# DummyLoad.net
KiCad netlist of a schematic drawn in EAGLE
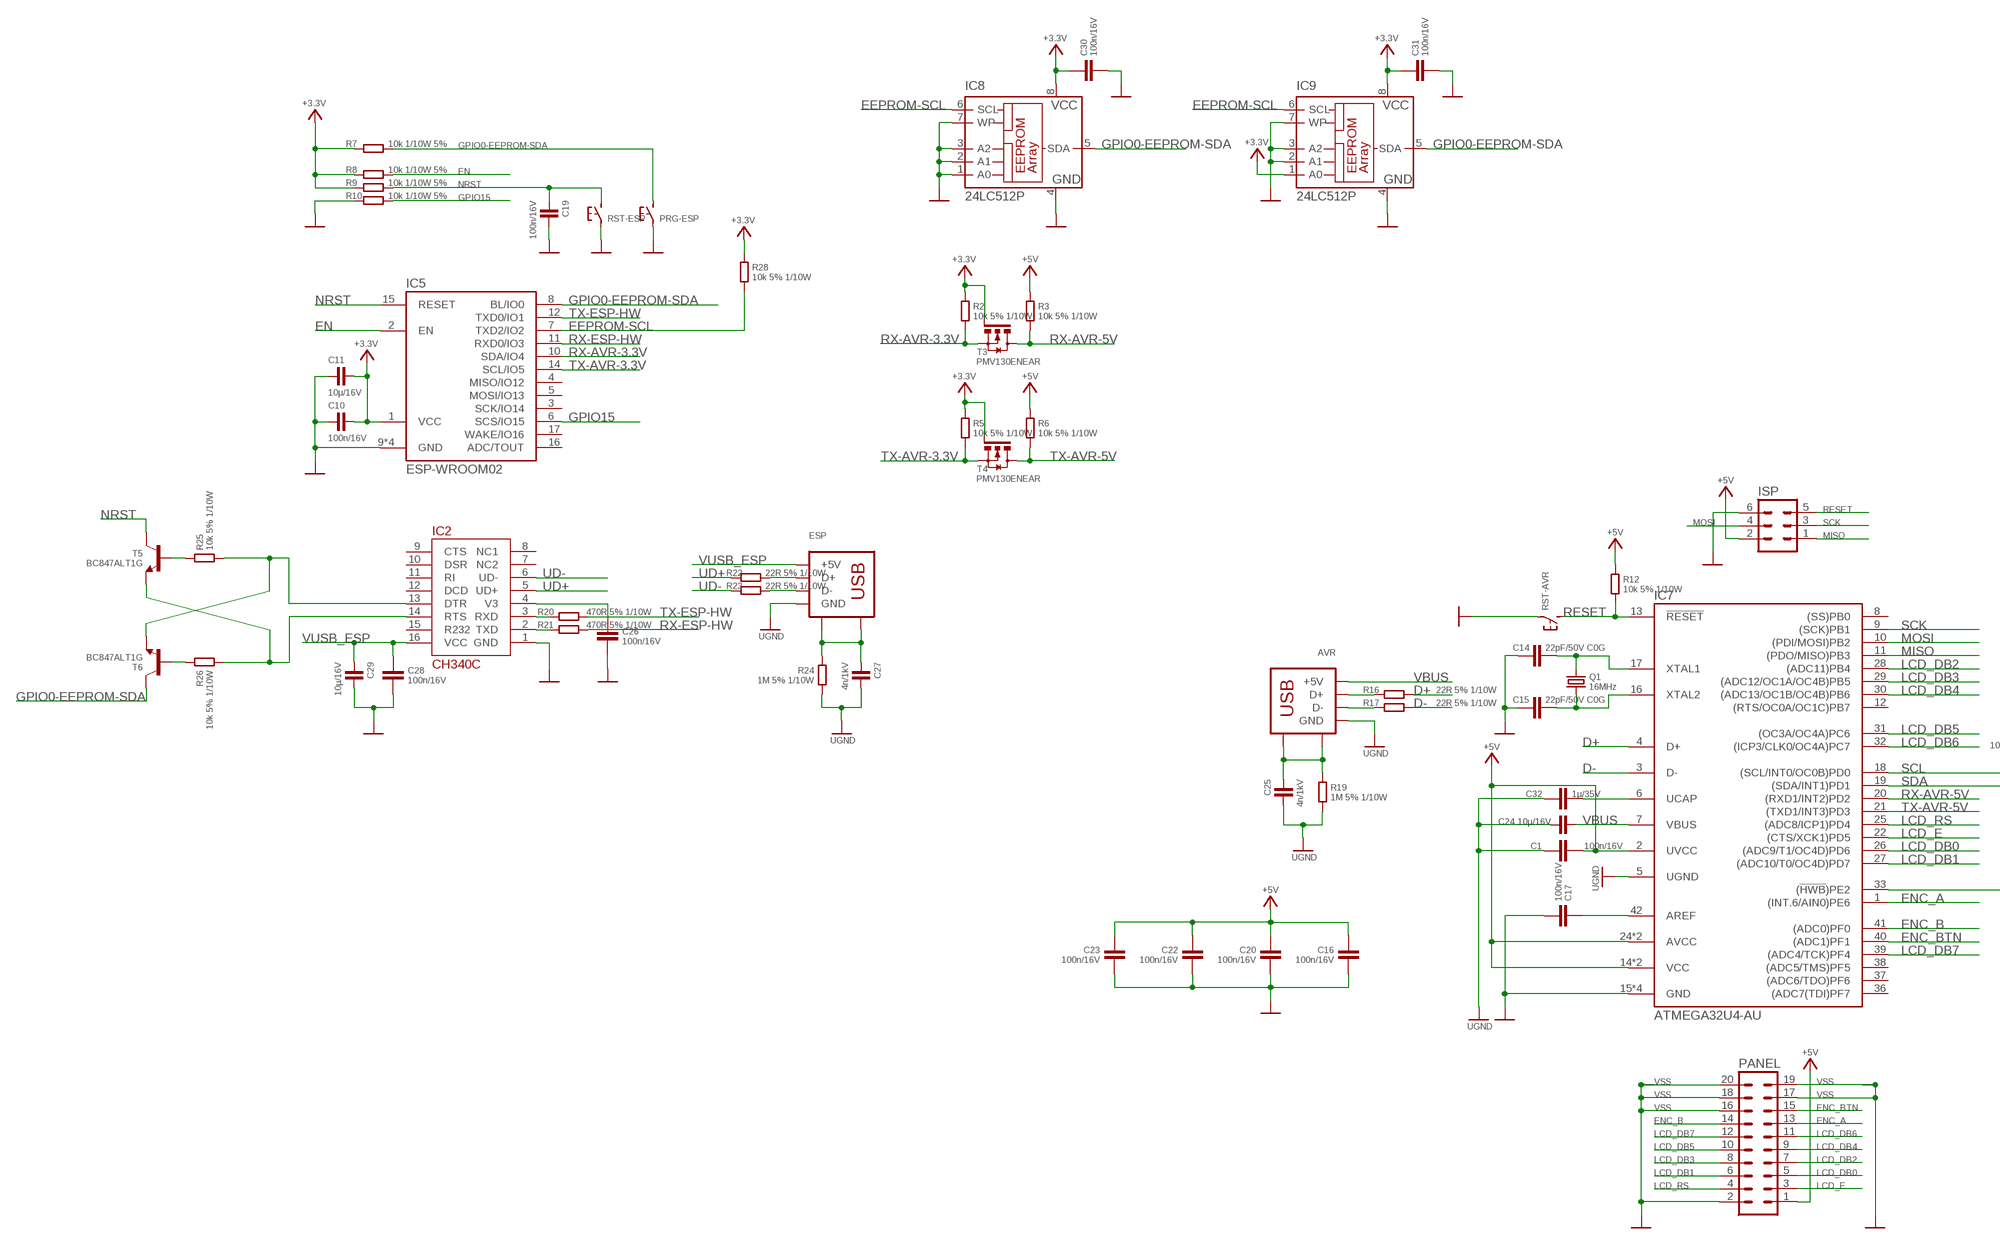
[diagram p0: schematic, sheet 1, part 1 of 2]
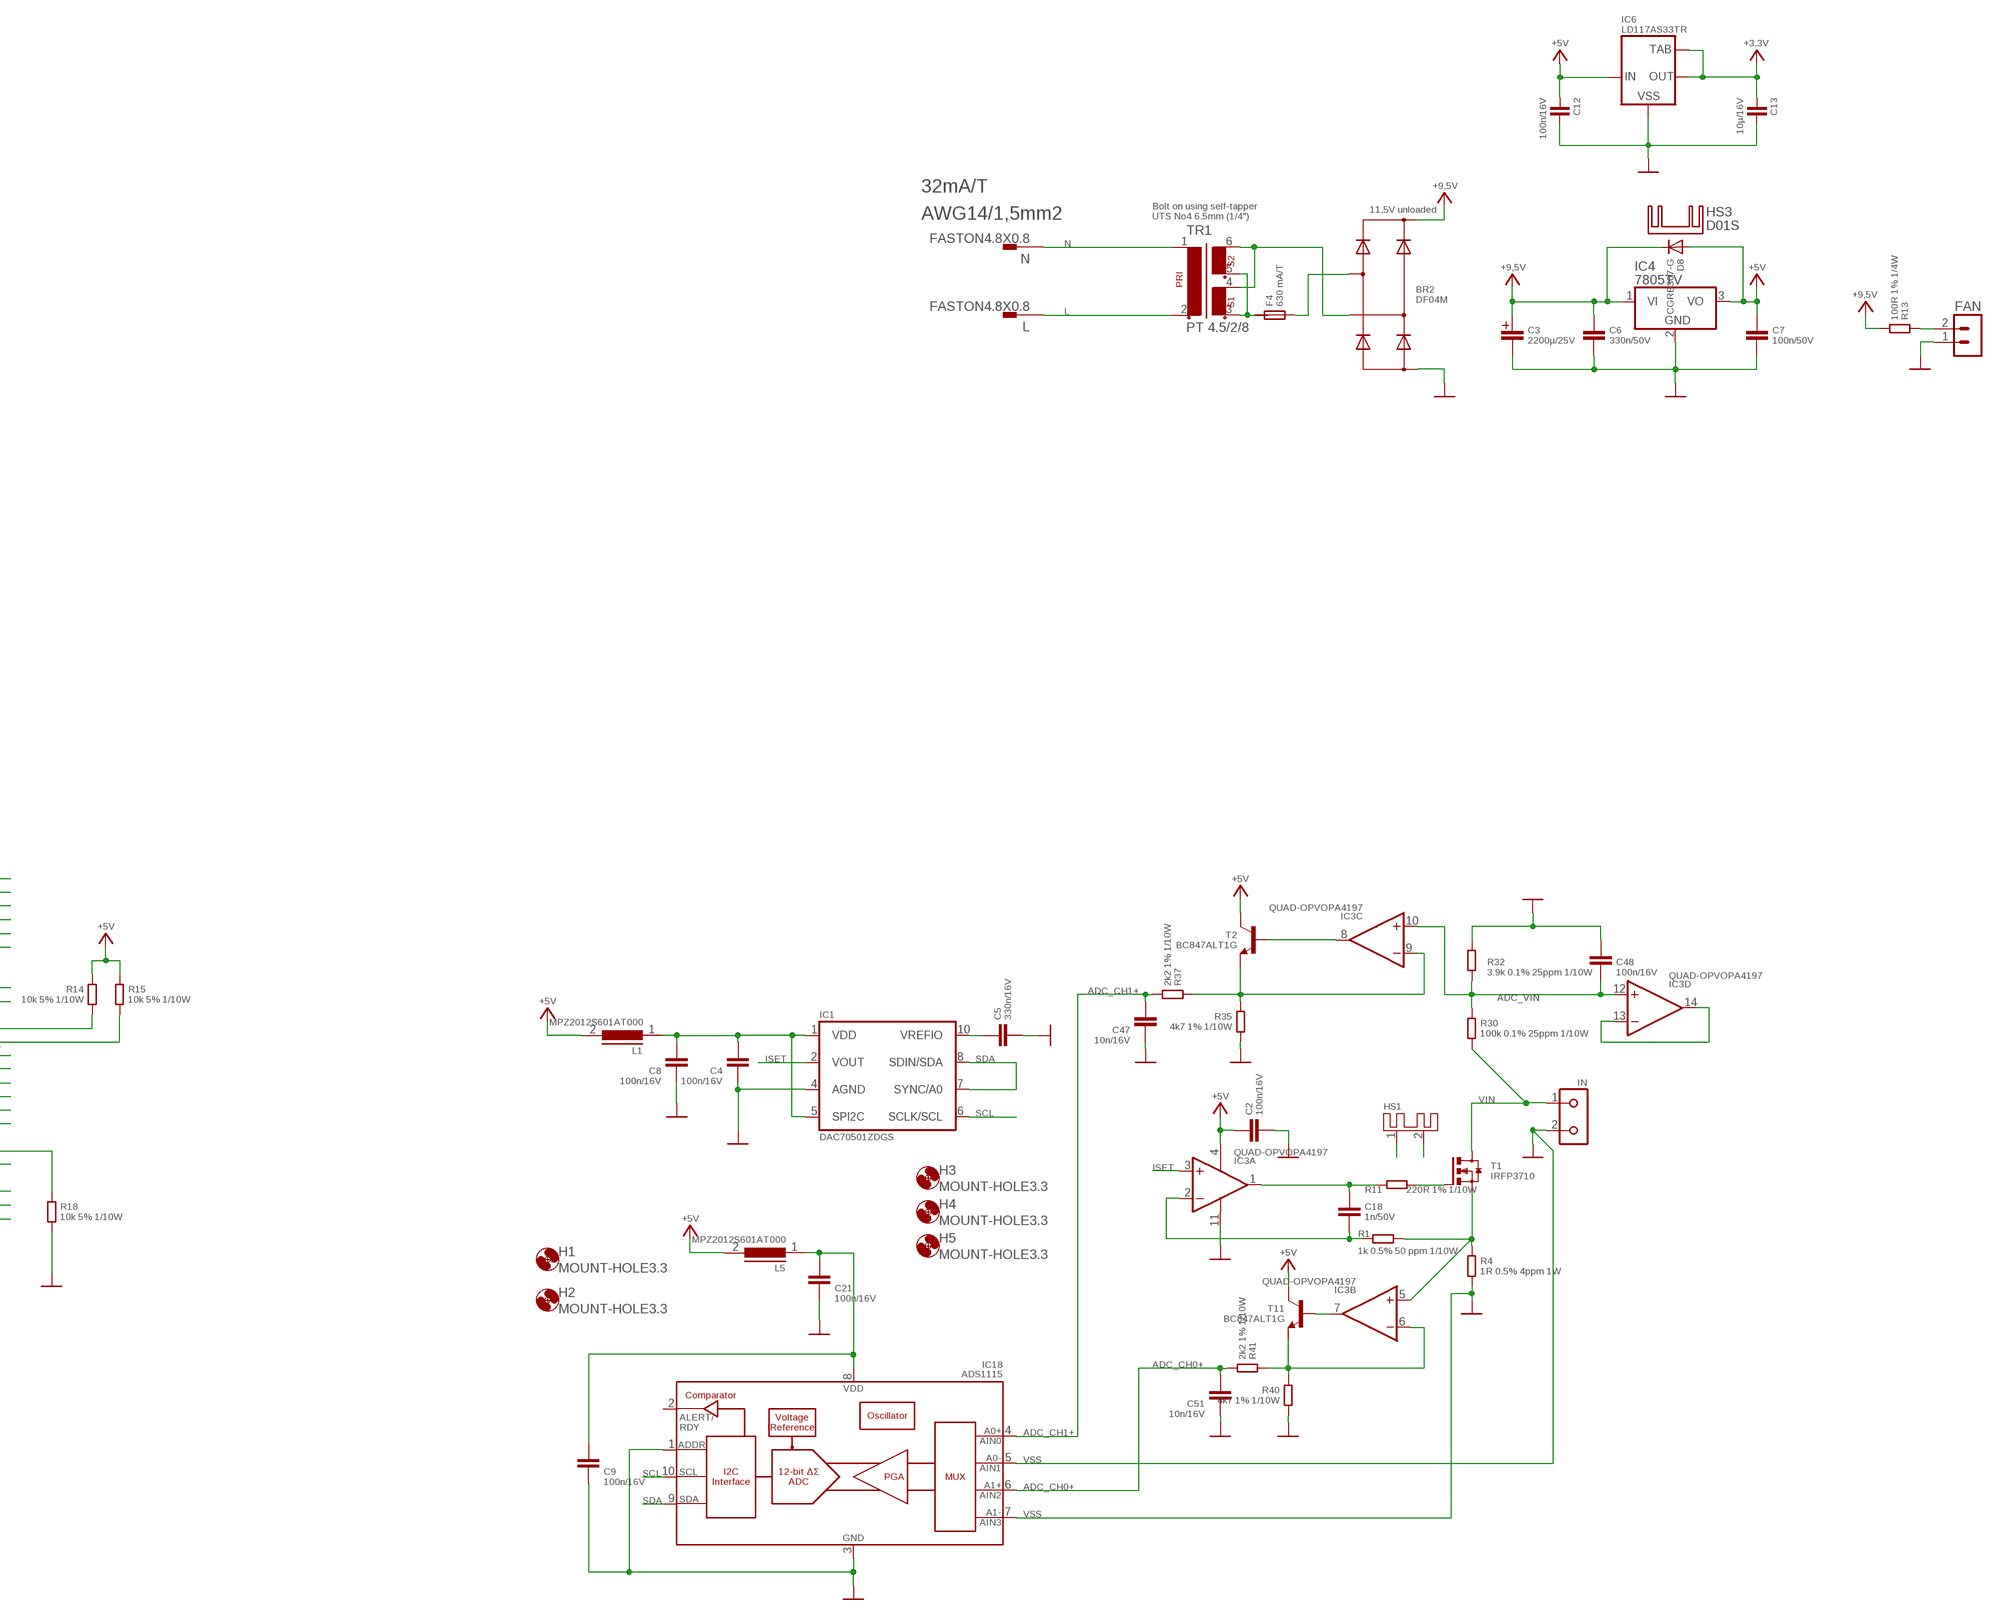
[diagram p1: schematic, sheet 1, part 2 of 2]

(export (version "E")
  (design (tool "Eeschema 10.0.6"))
  (components
    (comp (ref "AVR")
      (value "USBUSB-B")
      (footprint "eagle-import:USB-B")
      (libsource (lib "eagle-import") (part "USBUSB-B"))
    )
    (comp (ref "BR2")
      (value "DF04M")
      (footprint "eagle-import:BR-DIL2")
      (libsource (lib "eagle-import") (part "BRDIL2"))
    )
    (comp (ref "C1")
      (value "100n/16V")
      (footprint "eagle-import:0805")
      (libsource (lib "eagle-import") (part "CC/0805"))
    )
    (comp (ref "C2")
      (value "100n/16V")
      (footprint "eagle-import:0805")
      (libsource (lib "eagle-import") (part "CC/0805"))
    )
    (comp (ref "C3")
      (value "2200µ/25V")
      (footprint "eagle-import:C+_5_12.5")
      (libsource (lib "eagle-import") (part "C+5/12.5"))
    )
    (comp (ref "C4")
      (value "100n/16V")
      (footprint "eagle-import:0805")
      (libsource (lib "eagle-import") (part "CC/0805"))
    )
    (comp (ref "C5")
      (value "330n/16V")
      (footprint "eagle-import:0805")
      (libsource (lib "eagle-import") (part "CC/0805"))
    )
    (comp (ref "C6")
      (value "330n/50V")
      (footprint "eagle-import:0805")
      (libsource (lib "eagle-import") (part "CC/0805"))
    )
    (comp (ref "C7")
      (value "100n/50V")
      (footprint "eagle-import:0805")
      (libsource (lib "eagle-import") (part "CC/0805"))
    )
    (comp (ref "C8")
      (value "100n/16V")
      (footprint "eagle-import:0805")
      (libsource (lib "eagle-import") (part "CC/0805"))
    )
    (comp (ref "C9")
      (value "100n/16V")
      (footprint "eagle-import:0805")
      (libsource (lib "eagle-import") (part "CC/0805"))
    )
    (comp (ref "C10")
      (value "100n/16V")
      (footprint "eagle-import:C0805")
      (libsource (lib "eagle-import") (part "CAPACITOR-0805"))
    )
    (comp (ref "C11")
      (value "10µ/16V")
      (footprint "eagle-import:C1210")
      (libsource (lib "eagle-import") (part "CAPACITOR-1210"))
    )
    (comp (ref "C12")
      (value "100n/16V")
      (footprint "eagle-import:C0805")
      (libsource (lib "eagle-import") (part "CAPACITOR-0805"))
    )
    (comp (ref "C13")
      (value "10µ/16V")
      (footprint "eagle-import:C1210")
      (libsource (lib "eagle-import") (part "CAPACITOR-1210"))
    )
    (comp (ref "C14")
      (value "22pF/50V C0G")
      (footprint "eagle-import:0805")
      (libsource (lib "eagle-import") (part "CC/0805"))
    )
    (comp (ref "C15")
      (value "22pF/50V C0G")
      (footprint "eagle-import:0805")
      (libsource (lib "eagle-import") (part "CC/0805"))
    )
    (comp (ref "C16")
      (value "100n/16V")
      (footprint "eagle-import:0805")
      (libsource (lib "eagle-import") (part "CC/0805"))
    )
    (comp (ref "C17")
      (value "100n/16V")
      (footprint "eagle-import:0805")
      (libsource (lib "eagle-import") (part "CC/0805"))
    )
    (comp (ref "C18")
      (value "1n/50V")
      (footprint "eagle-import:0805")
      (libsource (lib "eagle-import") (part "CC/0805"))
    )
    (comp (ref "C19")
      (value "100n/16V")
      (footprint "eagle-import:C0805")
      (libsource (lib "eagle-import") (part "CAPACITOR-0805"))
    )
    (comp (ref "C20")
      (value "100n/16V")
      (footprint "eagle-import:0805")
      (libsource (lib "eagle-import") (part "CC/0805"))
    )
    (comp (ref "C21")
      (value "100n/16V")
      (footprint "eagle-import:0805")
      (libsource (lib "eagle-import") (part "CC/0805"))
    )
    (comp (ref "C22")
      (value "100n/16V")
      (footprint "eagle-import:0805")
      (libsource (lib "eagle-import") (part "CC/0805"))
    )
    (comp (ref "C23")
      (value "100n/16V")
      (footprint "eagle-import:0805")
      (libsource (lib "eagle-import") (part "CC/0805"))
    )
    (comp (ref "C24")
      (value "10µ/16V")
      (footprint "eagle-import:C1210")
      (libsource (lib "eagle-import") (part "CAPACITOR-1210"))
    )
    (comp (ref "C25")
      (value "4n/1kV")
      (footprint "eagle-import:C1206")
      (libsource (lib "eagle-import") (part "CAPACITOR-1206"))
    )
    (comp (ref "C26")
      (value "100n/16V")
      (footprint "eagle-import:0805")
      (libsource (lib "eagle-import") (part "CC/0805"))
    )
    (comp (ref "C27")
      (value "4n/1kV")
      (footprint "eagle-import:C1206")
      (libsource (lib "eagle-import") (part "CAPACITOR-1206"))
    )
    (comp (ref "C28")
      (value "100n/16V")
      (footprint "eagle-import:0805")
      (libsource (lib "eagle-import") (part "CC/0805"))
    )
    (comp (ref "C29")
      (value "10µ/16V")
      (footprint "eagle-import:C1210")
      (libsource (lib "eagle-import") (part "CAPACITOR-1210"))
    )
    (comp (ref "C30")
      (value "100n/16V")
      (footprint "eagle-import:0805")
      (libsource (lib "eagle-import") (part "CC/0805"))
    )
    (comp (ref "C31")
      (value "100n/16V")
      (footprint "eagle-import:0805")
      (libsource (lib "eagle-import") (part "CC/0805"))
    )
    (comp (ref "C32")
      (value "1µ/35V")
      (footprint "eagle-import:0805")
      (libsource (lib "eagle-import") (part "CC/0805"))
    )
    (comp (ref "C47")
      (value "10n/16V")
      (footprint "eagle-import:0805")
      (libsource (lib "eagle-import") (part "CC/0805"))
    )
    (comp (ref "C48")
      (value "100n/16V")
      (footprint "eagle-import:0805")
      (libsource (lib "eagle-import") (part "CC/0805"))
    )
    (comp (ref "C51")
      (value "10n/16V")
      (footprint "eagle-import:0805")
      (libsource (lib "eagle-import") (part "CC/0805"))
    )
    (comp (ref "D8")
      (value "CGRB307-G")
      (footprint "eagle-import:DO214AA-CGRB307-G")
      (libsource (lib "eagle-import") (part "DWIDE"))
    )
    (comp (ref "ESP")
      (value "USBUSB-B")
      (footprint "eagle-import:USB-B")
      (libsource (lib "eagle-import") (part "USBUSB-B"))
    )
    (comp (ref "F4")
      (value "630 mA/T")
      (footprint "eagle-import:F5X20")
      (libsource (lib "eagle-import") (part "F5X20"))
    )
    (comp (ref "FAN")
      (value "JST-PH-2.0-2P")
      (footprint "eagle-import:JST-PH-2.0-2P")
      (libsource (lib "eagle-import") (part "JST-PH-2.0-2P"))
    )
    (comp (ref "H1")
      (value "MOUNT-HOLE3.3")
      (footprint "eagle-import:3,3")
      (libsource (lib "eagle-import") (part "MOUNT-HOLE3.3"))
    )
    (comp (ref "H2")
      (value "MOUNT-HOLE3.3")
      (footprint "eagle-import:3,3")
      (libsource (lib "eagle-import") (part "MOUNT-HOLE3.3"))
    )
    (comp (ref "H3")
      (value "MOUNT-HOLE3.3")
      (footprint "eagle-import:3,3")
      (libsource (lib "eagle-import") (part "MOUNT-HOLE3.3"))
    )
    (comp (ref "H4")
      (value "MOUNT-HOLE3.3")
      (footprint "eagle-import:3,3")
      (libsource (lib "eagle-import") (part "MOUNT-HOLE3.3"))
    )
    (comp (ref "H5")
      (value "MOUNT-HOLE3.3")
      (footprint "eagle-import:3,3")
      (libsource (lib "eagle-import") (part "MOUNT-HOLE3.3"))
    )
    (comp (ref "HS1")
      (value "HSCR201-50")
      (footprint "eagle-import:CR201-50")
      (libsource (lib "eagle-import") (part "HSCR201-50"))
    )
    (comp (ref "HS3")
      (value "D01S")
      (footprint "eagle-import:D01S")
      (libsource (lib "eagle-import") (part "D01S"))
    )
    (comp (ref "IC1")
      (value "DAC70501ZDGS")
      (footprint "eagle-import:VSSOP10")
      (libsource (lib "eagle-import") (part "DAC70501"))
    )
    (comp (ref "IC2")
      (value "CH340C")
      (footprint "eagle-import:SOP16")
      (libsource (lib "eagle-import") (part "CH340C"))
    )
    (comp (ref "IC3")
      (value "QUAD-OPVOPA4197")
      (footprint "eagle-import:SO14")
      (fields (field (name "OC_MOUSER") "595-OPA4197IDR"))
      (libsource (lib "eagle-import") (part "QUAD-OPVOPA4197"))
    )
    (comp (ref "IC4")
      (value "7805TV")
      (footprint "eagle-import:TO220V")
      (libsource (lib "eagle-import") (part "78TV05"))
    )
    (comp (ref "IC5")
      (value "ESP-WROOM02")
      (footprint "eagle-import:ESP-WROOM02")
      (libsource (lib "eagle-import") (part "ESP-WROOM02"))
    )
    (comp (ref "IC6")
      (value "LD117AS33TR")
      (footprint "eagle-import:SOT223")
      (libsource (lib "eagle-import") (part "LD117A?S33TR"))
    )
    (comp (ref "IC7")
      (value "ATMEGA32U4-AU")
      (footprint "eagle-import:TQFP44")
      (libsource (lib "eagle-import") (part "ATMEGA32U4-AU"))
    )
    (comp (ref "IC8")
      (value "24LC512P")
      (footprint "eagle-import:DIL8")
      (fields (field (name "MF") "MICROCHIP") (field (name "MPN") "24LC256-E/P"))
      (libsource (lib "eagle-import") (part "24PLC256"))
    )
    (comp (ref "IC9")
      (value "24LC512P")
      (footprint "eagle-import:DIL8")
      (fields (field (name "MF") "MICROCHIP") (field (name "MPN") "24LC256-E/P"))
      (libsource (lib "eagle-import") (part "24PLC256"))
    )
    (comp (ref "IC18")
      (value "ADS1115")
      (footprint "eagle-import:VSSOP10")
      (libsource (lib "eagle-import") (part "ADS1015VSSOP10"))
    )
    (comp (ref "IN")
      (value "KL2691311500002")
      (footprint "eagle-import:KL2-691311500002")
      (libsource (lib "eagle-import") (part "KL2691311500002"))
    )
    (comp (ref "ISP")
      (value "ML6")
      (footprint "eagle-import:ML6")
      (libsource (lib "eagle-import") (part "ML6"))
    )
    (comp (ref "L")
      (value "FASTON4.8X0.8")
      (footprint "eagle-import:FASTON-4.8X0.8")
      (libsource (lib "eagle-import") (part "FASTON4.8X0.8"))
    )
    (comp (ref "L1")
      (value "MPZ2012S601AT000")
      (footprint "eagle-import:C0805K@1")
      (libsource (lib "eagle-import") (part "L0805"))
    )
    (comp (ref "L5")
      (value "MPZ2012S601AT000")
      (footprint "eagle-import:C0805K@1")
      (libsource (lib "eagle-import") (part "L0805"))
    )
    (comp (ref "N")
      (value "FASTON4.8X0.8")
      (footprint "eagle-import:FASTON-4.8X0.8")
      (libsource (lib "eagle-import") (part "FASTON4.8X0.8"))
    )
    (comp (ref "PANEL")
      (value "MA10-2")
      (footprint "eagle-import:MA10-2")
      (libsource (lib "eagle-import") (part "MA10-2"))
    )
    (comp (ref "PRG-ESP")
      (value "TS1B3F-10XX")
      (footprint "eagle-import:B3F-10XX")
      (libsource (lib "eagle-import") (part "TS1B3F-10XX"))
    )
    (comp (ref "Q1")
      (value "16MHz")
      (footprint "eagle-import:Q-5X3.2MM-TXC-7A.SERIES")
      (libsource (lib "eagle-import") (part "Q5X3.2MM-TXC-7A-SERIES"))
    )
    (comp (ref "R1")
      (value "1k 0.5% 50 ppm 1/10W")
      (footprint "eagle-import:C0805K")
      (libsource (lib "eagle-import") (part "R-SMD0805"))
    )
    (comp (ref "R2")
      (value "10k 5% 1/10W")
      (footprint "eagle-import:C0805K")
      (libsource (lib "eagle-import") (part "R-SMD0805"))
    )
    (comp (ref "R3")
      (value "10k 5% 1/10W")
      (footprint "eagle-import:C0805K")
      (libsource (lib "eagle-import") (part "R-SMD0805"))
    )
    (comp (ref "R4")
      (value "1R 0.5% 4ppm 1W")
      (footprint "eagle-import:R-SHUNT-VSR")
      (libsource (lib "eagle-import") (part "R-SHUNTVSR"))
    )
    (comp (ref "R5")
      (value "10k 5% 1/10W")
      (footprint "eagle-import:C0805K")
      (libsource (lib "eagle-import") (part "R-SMD0805"))
    )
    (comp (ref "R6")
      (value "10k 5% 1/10W")
      (footprint "eagle-import:C0805K")
      (libsource (lib "eagle-import") (part "R-SMD0805"))
    )
    (comp (ref "R7")
      (value "10k 1/10W 5%")
      (footprint "eagle-import:C0805K")
      (libsource (lib "eagle-import") (part "R-SMD0805"))
    )
    (comp (ref "R8")
      (value "10k 1/10W 5%")
      (footprint "eagle-import:C0805K")
      (libsource (lib "eagle-import") (part "R-SMD0805"))
    )
    (comp (ref "R9")
      (value "10k 1/10W 5%")
      (footprint "eagle-import:C0805K")
      (libsource (lib "eagle-import") (part "R-SMD0805"))
    )
    (comp (ref "R10")
      (value "10k 1/10W 5%")
      (footprint "eagle-import:C0805K")
      (libsource (lib "eagle-import") (part "R-SMD0805"))
    )
    (comp (ref "R11")
      (value "220R 1% 1/10W")
      (footprint "eagle-import:C0805K")
      (libsource (lib "eagle-import") (part "R-SMD0805"))
    )
    (comp (ref "R12")
      (value "10k 5% 1/10W")
      (footprint "eagle-import:C0805K")
      (libsource (lib "eagle-import") (part "R-SMD0805"))
    )
    (comp (ref "R13")
      (value "100R 1% 1/4W")
      (footprint "eagle-import:C0805K")
      (libsource (lib "eagle-import") (part "R-SMD0805"))
    )
    (comp (ref "R14")
      (value "10k 5% 1/10W")
      (footprint "eagle-import:C0805K")
      (libsource (lib "eagle-import") (part "R-SMD0805"))
    )
    (comp (ref "R15")
      (value "10k 5% 1/10W")
      (footprint "eagle-import:C0805K")
      (libsource (lib "eagle-import") (part "R-SMD0805"))
    )
    (comp (ref "R16")
      (value "22R 5% 1/10W")
      (footprint "eagle-import:C0805K")
      (libsource (lib "eagle-import") (part "R-SMD0805"))
    )
    (comp (ref "R17")
      (value "22R 5% 1/10W")
      (footprint "eagle-import:C0805K")
      (libsource (lib "eagle-import") (part "R-SMD0805"))
    )
    (comp (ref "R18")
      (value "10k 5% 1/10W")
      (footprint "eagle-import:C0805K")
      (libsource (lib "eagle-import") (part "R-SMD0805"))
    )
    (comp (ref "R19")
      (value "1M 5% 1/10W")
      (footprint "eagle-import:C0805K")
      (libsource (lib "eagle-import") (part "R-SMD0805"))
    )
    (comp (ref "R20")
      (value "470R 5% 1/10W")
      (footprint "eagle-import:C0805K")
      (libsource (lib "eagle-import") (part "R-SMD0805"))
    )
    (comp (ref "R21")
      (value "470R 5% 1/10W")
      (footprint "eagle-import:C0805K")
      (libsource (lib "eagle-import") (part "R-SMD0805"))
    )
    (comp (ref "R22")
      (value "22R 5% 1/10W")
      (footprint "eagle-import:C0805K")
      (libsource (lib "eagle-import") (part "R-SMD0805"))
    )
    (comp (ref "R23")
      (value "22R 5% 1/10W")
      (footprint "eagle-import:C0805K")
      (libsource (lib "eagle-import") (part "R-SMD0805"))
    )
    (comp (ref "R24")
      (value "1M 5% 1/10W")
      (footprint "eagle-import:C0805K")
      (libsource (lib "eagle-import") (part "R-SMD0805"))
    )
    (comp (ref "R25")
      (value "10k 5% 1/10W")
      (footprint "eagle-import:C0805K")
      (libsource (lib "eagle-import") (part "R-SMD0805"))
    )
    (comp (ref "R26")
      (value "10k 5% 1/10W")
      (footprint "eagle-import:C0805K")
      (libsource (lib "eagle-import") (part "R-SMD0805"))
    )
    (comp (ref "R28")
      (value "10k 5% 1/10W")
      (footprint "eagle-import:C0805K")
      (libsource (lib "eagle-import") (part "R-SMD0805"))
    )
    (comp (ref "R30")
      (value "100k 0.1% 25ppm 1/10W")
      (footprint "eagle-import:C0805K")
      (libsource (lib "eagle-import") (part "R-SMD0805"))
    )
    (comp (ref "R32")
      (value "3.9k 0.1% 25ppm 1/10W")
      (footprint "eagle-import:C0805K")
      (libsource (lib "eagle-import") (part "R-SMD0805"))
    )
    (comp (ref "R35")
      (value "4k7 1% 1/10W")
      (footprint "eagle-import:C0805K")
      (libsource (lib "eagle-import") (part "R-SMD0805"))
    )
    (comp (ref "R37")
      (value "2k2 1% 1/10W")
      (footprint "eagle-import:C0805K")
      (libsource (lib "eagle-import") (part "R-SMD0805"))
    )
    (comp (ref "R40")
      (value "4k7 1% 1/10W")
      (footprint "eagle-import:C0805K")
      (libsource (lib "eagle-import") (part "R-SMD0805"))
    )
    (comp (ref "R41")
      (value "2k2 1% 1/10W")
      (footprint "eagle-import:C0805K")
      (libsource (lib "eagle-import") (part "R-SMD0805"))
    )
    (comp (ref "RST-AVR")
      (value "TS1B3F-10XX")
      (footprint "eagle-import:B3F-10XX")
      (libsource (lib "eagle-import") (part "TS1B3F-10XX"))
    )
    (comp (ref "RST-ESP")
      (value "TS1B3F-10XX")
      (footprint "eagle-import:B3F-10XX")
      (libsource (lib "eagle-import") (part "TS1B3F-10XX"))
    )
    (comp (ref "T1")
      (value "IRFP3710")
      (footprint "eagle-import:TOP3AV")
      (libsource (lib "eagle-import") (part "T-NMOSTO247"))
    )
    (comp (ref "T2")
      (value "BC847ALT1G")
      (footprint "eagle-import:SOT23-BEC")
      (libsource (lib "eagle-import") (part "T-NPNSOT23-BEC"))
    )
    (comp (ref "T3")
      (value "PMV130ENEAR")
      (footprint "eagle-import:SOT23")
      (libsource (lib "eagle-import") (part "T-NMOSIRLML2502PBF"))
    )
    (comp (ref "T4")
      (value "PMV130ENEAR")
      (footprint "eagle-import:SOT23")
      (libsource (lib "eagle-import") (part "T-NMOSIRLML2502PBF"))
    )
    (comp (ref "T5")
      (value "BC847ALT1G")
      (footprint "eagle-import:SOT23-BEC")
      (libsource (lib "eagle-import") (part "T-NPNSOT23-BEC"))
    )
    (comp (ref "T6")
      (value "BC847ALT1G")
      (footprint "eagle-import:SOT23-BEC")
      (libsource (lib "eagle-import") (part "T-NPNSOT23-BEC"))
    )
    (comp (ref "T11")
      (value "BC847ALT1G")
      (footprint "eagle-import:SOT23-BEC")
      (libsource (lib "eagle-import") (part "T-NPNSOT23-BEC"))
    )
    (comp (ref "TR1")
      (value "PT 4.5/2/8")
      (footprint "eagle-import:PT_4,5_2_..")
      (libsource (lib "eagle-import") (part "PT4,5/2/.."))
    )
  )
  (nets
    (net (code "1") (name "+3.3V") (class "Default")
      (node (ref "C10") (pin "2") (pinfunction "2_2") (pintype "passive"))
      (node (ref "C11") (pin "2") (pinfunction "2_2") (pintype "passive"))
      (node (ref "C13") (pin "1") (pinfunction "1_1") (pintype "passive"))
      (node (ref "C30") (pin "1") (pinfunction "1_1") (pintype "passive"))
      (node (ref "C31") (pin "1") (pinfunction "1_1") (pintype "passive"))
      (node (ref "IC5") (pin "1") (pinfunction "VCC_1") (pintype "power_in"))
      (node (ref "IC6") (pin "2") (pinfunction "OUT_2") (pintype "passive"))
      (node (ref "IC6") (pin "4") (pinfunction "OUT1_4") (pintype "passive"))
      (node (ref "IC8") (pin "8") (pinfunction "VCC_8") (pintype "power_in"))
      (node (ref "IC9") (pin "1") (pinfunction "A0_1") (pintype "input"))
      (node (ref "IC9") (pin "8") (pinfunction "VCC_8") (pintype "power_in"))
      (node (ref "R2") (pin "1") (pinfunction "1_1") (pintype "passive"))
      (node (ref "R28") (pin "1") (pinfunction "1_1") (pintype "passive"))
      (node (ref "R5") (pin "1") (pinfunction "1_1") (pintype "passive"))
      (node (ref "R7") (pin "1") (pinfunction "1_1") (pintype "passive"))
      (node (ref "R8") (pin "1") (pinfunction "1_1") (pintype "passive"))
      (node (ref "R9") (pin "1") (pinfunction "1_1") (pintype "passive"))
      (node (ref "T3") (pin "1") (pinfunction "G_1") (pintype "passive"))
      (node (ref "T4") (pin "1") (pinfunction "G_1") (pintype "passive"))
    )
    (net (code "2") (name "+5V") (class "Default")
      (node (ref "C1") (pin "2") (pinfunction "2_2") (pintype "passive"))
      (node (ref "C12") (pin "1") (pinfunction "1_1") (pintype "passive"))
      (node (ref "C16") (pin "1") (pinfunction "1_1") (pintype "passive"))
      (node (ref "C2") (pin "1") (pinfunction "1_1") (pintype "passive"))
      (node (ref "C20") (pin "1") (pinfunction "1_1") (pintype "passive"))
      (node (ref "C22") (pin "1") (pinfunction "1_1") (pintype "passive"))
      (node (ref "C23") (pin "1") (pinfunction "1_1") (pintype "passive"))
      (node (ref "C7") (pin "1") (pinfunction "1_1") (pintype "passive"))
      (node (ref "D8") (pin "A") (pinfunction "A_A") (pintype "passive"))
      (node (ref "IC3") (pin "4") (pinfunction "V+_4") (pintype "power_in"))
      (node (ref "IC4") (pin "3") (pinfunction "VO_3") (pintype "passive"))
      (node (ref "IC6") (pin "3") (pinfunction "IN_3") (pintype "input"))
      (node (ref "IC7") (pin "14") (pinfunction "VCC_14") (pintype "power_in"))
      (node (ref "IC7") (pin "2") (pinfunction "UVCC_2") (pintype "power_in"))
      (node (ref "IC7") (pin "24") (pinfunction "AVCC_24") (pintype "power_in"))
      (node (ref "IC7") (pin "34") (pinfunction "VCC_34") (pintype "power_in"))
      (node (ref "IC7") (pin "44") (pinfunction "AVCC_44") (pintype "power_in"))
      (node (ref "ISP") (pin "2") (pinfunction "2_2") (pintype "passive"))
      (node (ref "L1") (pin "2") (pinfunction "2_2") (pintype "passive"))
      (node (ref "L5") (pin "2") (pinfunction "2_2") (pintype "passive"))
      (node (ref "PANEL") (pin "1") (pinfunction "1_1") (pintype "passive"))
      (node (ref "R12") (pin "1") (pinfunction "1_1") (pintype "passive"))
      (node (ref "R14") (pin "1") (pinfunction "1_1") (pintype "passive"))
      (node (ref "R15") (pin "1") (pinfunction "1_1") (pintype "passive"))
      (node (ref "R3") (pin "1") (pinfunction "1_1") (pintype "passive"))
      (node (ref "R6") (pin "1") (pinfunction "1_1") (pintype "passive"))
      (node (ref "T11") (pin "C") (pinfunction "C_C") (pintype "passive"))
      (node (ref "T2") (pin "C") (pinfunction "C_C") (pintype "passive"))
    )
    (net (code "3") (name "+9,5V") (class "Default")
      (node (ref "BR2") (pin "DC+") (pinfunction "DC+_DC+") (pintype "passive"))
      (node (ref "C3") (pin "+") (pinfunction "+_+") (pintype "passive"))
      (node (ref "C6") (pin "1") (pinfunction "1_1") (pintype "passive"))
      (node (ref "D8") (pin "C") (pinfunction "C_C") (pintype "passive"))
      (node (ref "IC4") (pin "1") (pinfunction "VI_1") (pintype "input"))
      (node (ref "R13") (pin "2") (pinfunction "2_2") (pintype "passive"))
    )
    (net (code "4") (name "/ADC_CH0+") (class "Default")
      (node (ref "C51") (pin "1") (pinfunction "1_1") (pintype "passive"))
      (node (ref "IC18") (pin "6") (pinfunction "AIN2_6") (pintype "bidirectional"))
      (node (ref "R41") (pin "2") (pinfunction "2_2") (pintype "passive"))
    )
    (net (code "5") (name "/ADC_CH1+") (class "Default")
      (node (ref "C47") (pin "1") (pinfunction "1_1") (pintype "passive"))
      (node (ref "IC18") (pin "4") (pinfunction "AIN0_4") (pintype "bidirectional"))
      (node (ref "R37") (pin "2") (pinfunction "2_2") (pintype "passive"))
    )
    (net (code "6") (name "/ADC_VIN") (class "Default")
      (node (ref "C48") (pin "2") (pinfunction "2_2") (pintype "passive"))
      (node (ref "IC3") (pin "10") (pinfunction "+IN_10") (pintype "input"))
      (node (ref "IC3") (pin "12") (pinfunction "+IN_12") (pintype "input"))
      (node (ref "R30") (pin "1") (pinfunction "1_1") (pintype "passive"))
      (node (ref "R32") (pin "2") (pinfunction "2_2") (pintype "passive"))
    )
    (net (code "7") (name "/D+") (class "Default")
      (node (ref "IC7") (pin "4") (pinfunction "D+_4") (pintype "bidirectional"))
      (node (ref "R16") (pin "1") (pinfunction "1_1") (pintype "passive"))
    )
    (net (code "8") (name "/D-") (class "Default")
      (node (ref "IC7") (pin "3") (pinfunction "D-_3") (pintype "bidirectional"))
      (node (ref "R17") (pin "1") (pinfunction "1_1") (pintype "passive"))
    )
    (net (code "9") (name "/EEPROM-SCL") (class "Default")
      (node (ref "IC5") (pin "7") (pinfunction "TXD2/IO2_7") (pintype "bidirectional"))
      (node (ref "IC8") (pin "6") (pinfunction "SCL_6") (pintype "input"))
      (node (ref "IC9") (pin "6") (pinfunction "SCL_6") (pintype "input"))
      (node (ref "R28") (pin "2") (pinfunction "2_2") (pintype "passive"))
    )
    (net (code "10") (name "/EN") (class "Default")
      (node (ref "IC5") (pin "2") (pinfunction "EN_2") (pintype "bidirectional"))
      (node (ref "R8") (pin "2") (pinfunction "2_2") (pintype "passive"))
    )
    (net (code "11") (name "/ENC_A") (class "Default")
      (node (ref "IC7") (pin "1") (pinfunction "(INT.6/AIN0)PE6_1") (pintype "bidirectional"))
      (node (ref "PANEL") (pin "13") (pinfunction "13_13") (pintype "passive"))
    )
    (net (code "12") (name "/ENC_B") (class "Default")
      (node (ref "IC7") (pin "41") (pinfunction "(ADC0)PF0_41") (pintype "bidirectional"))
      (node (ref "PANEL") (pin "14") (pinfunction "14_14") (pintype "passive"))
    )
    (net (code "13") (name "/ENC_BTN") (class "Default")
      (node (ref "IC7") (pin "40") (pinfunction "(ADC1)PF1_40") (pintype "bidirectional"))
      (node (ref "PANEL") (pin "15") (pinfunction "15_15") (pintype "passive"))
    )
    (net (code "14") (name "/GPIO0-EEPROM-SDA") (class "Default")
      (node (ref "IC5") (pin "8") (pinfunction "BL/IO0_8") (pintype "bidirectional"))
      (node (ref "IC8") (pin "5") (pinfunction "SDA_5") (pintype "bidirectional"))
      (node (ref "IC9") (pin "5") (pinfunction "SDA_5") (pintype "bidirectional"))
      (node (ref "PRG-ESP") (pin "3") (pinfunction "2_3") (pintype "passive"))
      (node (ref "R7") (pin "2") (pinfunction "2_2") (pintype "passive"))
      (node (ref "T6") (pin "C") (pinfunction "C_C") (pintype "passive"))
    )
    (net (code "15") (name "/GPIO15") (class "Default")
      (node (ref "IC5") (pin "6") (pinfunction "SCS/IO15_6") (pintype "bidirectional"))
      (node (ref "R10") (pin "2") (pinfunction "2_2") (pintype "passive"))
    )
    (net (code "16") (name "/ISET") (class "Default")
      (node (ref "IC1") (pin "2") (pinfunction "VOUT_2") (pintype "output"))
      (node (ref "IC3") (pin "3") (pinfunction "+IN_3") (pintype "input"))
    )
    (net (code "17") (name "/L") (class "Default")
      (node (ref "L") (pin "A1") (pinfunction "1_A1") (pintype "passive"))
      (node (ref "L") (pin "A2") (pinfunction "1_A2") (pintype "passive"))
      (node (ref "TR1") (pin "2") (pinfunction "2_2") (pintype "passive"))
    )
    (net (code "18") (name "/LCD_DB0") (class "Default")
      (node (ref "IC7") (pin "26") (pinfunction "(ADC9/T1/OC4D)PD6_26") (pintype "bidirectional"))
      (node (ref "PANEL") (pin "5") (pinfunction "5_5") (pintype "passive"))
    )
    (net (code "19") (name "/LCD_DB1") (class "Default")
      (node (ref "IC7") (pin "27") (pinfunction "(ADC10/T0/OC4D)PD7_27") (pintype "bidirectional"))
      (node (ref "PANEL") (pin "6") (pinfunction "6_6") (pintype "passive"))
    )
    (net (code "20") (name "/LCD_DB2") (class "Default")
      (node (ref "IC7") (pin "28") (pinfunction "(ADC11)PB4_28") (pintype "bidirectional"))
      (node (ref "PANEL") (pin "7") (pinfunction "7_7") (pintype "passive"))
    )
    (net (code "21") (name "/LCD_DB3") (class "Default")
      (node (ref "IC7") (pin "29") (pinfunction "(ADC12/OC1A/OC4B)PB5_29") (pintype "bidirectional"))
      (node (ref "PANEL") (pin "8") (pinfunction "8_8") (pintype "passive"))
    )
    (net (code "22") (name "/LCD_DB4") (class "Default")
      (node (ref "IC7") (pin "30") (pinfunction "(ADC13/OC1B/OC4B)PB6_30") (pintype "bidirectional"))
      (node (ref "PANEL") (pin "9") (pinfunction "9_9") (pintype "passive"))
    )
    (net (code "23") (name "/LCD_DB5") (class "Default")
      (node (ref "IC7") (pin "31") (pinfunction "(OC3A/OC4A)PC6_31") (pintype "bidirectional"))
      (node (ref "PANEL") (pin "10") (pinfunction "10_10") (pintype "passive"))
    )
    (net (code "24") (name "/LCD_DB6") (class "Default")
      (node (ref "IC7") (pin "32") (pinfunction "(ICP3/CLK0/OC4A)PC7_32") (pintype "bidirectional"))
      (node (ref "PANEL") (pin "11") (pinfunction "11_11") (pintype "passive"))
    )
    (net (code "25") (name "/LCD_DB7") (class "Default")
      (node (ref "IC7") (pin "39") (pinfunction "(ADC4/TCK)PF4_39") (pintype "bidirectional"))
      (node (ref "PANEL") (pin "12") (pinfunction "12_12") (pintype "passive"))
    )
    (net (code "26") (name "/LCD_E") (class "Default")
      (node (ref "IC7") (pin "22") (pinfunction "(CTS/XCK1)PD5_22") (pintype "bidirectional"))
      (node (ref "PANEL") (pin "3") (pinfunction "3_3") (pintype "passive"))
    )
    (net (code "27") (name "/LCD_RS") (class "Default")
      (node (ref "IC7") (pin "25") (pinfunction "(ADC8/ICP1)PD4_25") (pintype "bidirectional"))
      (node (ref "PANEL") (pin "4") (pinfunction "4_4") (pintype "passive"))
    )
    (net (code "28") (name "/MISO") (class "Default")
      (node (ref "IC7") (pin "11") (pinfunction "(PDO/MISO)PB3_11") (pintype "bidirectional"))
      (node (ref "ISP") (pin "1") (pinfunction "1_1") (pintype "passive"))
    )
    (net (code "29") (name "/MOSI") (class "Default")
      (node (ref "IC7") (pin "10") (pinfunction "(PDI/MOSI)PB2_10") (pintype "bidirectional"))
      (node (ref "ISP") (pin "4") (pinfunction "4_4") (pintype "passive"))
    )
    (net (code "30") (name "/N") (class "Default")
      (node (ref "N") (pin "A1") (pinfunction "1_A1") (pintype "passive"))
      (node (ref "N") (pin "A2") (pinfunction "1_A2") (pintype "passive"))
      (node (ref "TR1") (pin "1") (pinfunction "1_1") (pintype "passive"))
    )
    (net (code "31") (name "/NRST") (class "Default")
      (node (ref "C19") (pin "1") (pinfunction "1_1") (pintype "passive"))
      (node (ref "IC5") (pin "15") (pinfunction "RESET_15") (pintype "bidirectional"))
      (node (ref "R9") (pin "2") (pinfunction "2_2") (pintype "passive"))
      (node (ref "RST-ESP") (pin "3") (pinfunction "2_3") (pintype "passive"))
      (node (ref "T5") (pin "C") (pinfunction "C_C") (pintype "passive"))
    )
    (net (code "32") (name "/RESET") (class "Default")
      (node (ref "IC7") (pin "13") (pinfunction "~{RESET}_13") (pintype "bidirectional"))
      (node (ref "ISP") (pin "5") (pinfunction "5_5") (pintype "passive"))
      (node (ref "R12") (pin "2") (pinfunction "2_2") (pintype "passive"))
      (node (ref "RST-AVR") (pin "3") (pinfunction "2_3") (pintype "passive"))
    )
    (net (code "33") (name "/RX-AVR-3.3V") (class "Default")
      (node (ref "IC5") (pin "10") (pinfunction "SDA/IO4_10") (pintype "bidirectional"))
      (node (ref "R2") (pin "2") (pinfunction "2_2") (pintype "passive"))
      (node (ref "T3") (pin "2") (pinfunction "S_2") (pintype "passive"))
    )
    (net (code "34") (name "/RX-AVR-5V") (class "Default")
      (node (ref "IC7") (pin "20") (pinfunction "(RXD1/INT2)PD2_20") (pintype "bidirectional"))
      (node (ref "R3") (pin "2") (pinfunction "2_2") (pintype "passive"))
      (node (ref "T3") (pin "3") (pinfunction "D_3") (pintype "passive"))
    )
    (net (code "35") (name "/RX-ESP-HW") (class "Default")
      (node (ref "IC5") (pin "11") (pinfunction "RXD0/IO3_11") (pintype "bidirectional"))
      (node (ref "R21") (pin "2") (pinfunction "2_2") (pintype "passive"))
    )
    (net (code "36") (name "/SCK") (class "Default")
      (node (ref "IC7") (pin "9") (pinfunction "(SCK)PB1_9") (pintype "bidirectional"))
      (node (ref "ISP") (pin "3") (pinfunction "3_3") (pintype "passive"))
    )
    (net (code "37") (name "/SCL") (class "Default")
      (node (ref "IC1") (pin "6") (pinfunction "SCLK/SCL_6") (pintype "input"))
      (node (ref "IC18") (pin "10") (pinfunction "SCL_10") (pintype "bidirectional"))
      (node (ref "IC7") (pin "18") (pinfunction "(SCL/INT0/OC0B)PD0_18") (pintype "bidirectional"))
      (node (ref "R14") (pin "2") (pinfunction "2_2") (pintype "passive"))
    )
    (net (code "38") (name "/SDA") (class "Default")
      (node (ref "IC1") (pin "7") (pinfunction "SYNC/A0_7") (pintype "input"))
      (node (ref "IC1") (pin "8") (pinfunction "SDIN/SDA_8") (pintype "input"))
      (node (ref "IC18") (pin "9") (pinfunction "SDA_9") (pintype "bidirectional"))
      (node (ref "IC7") (pin "19") (pinfunction "(SDA/INT1)PD1_19") (pintype "bidirectional"))
      (node (ref "R15") (pin "2") (pinfunction "2_2") (pintype "passive"))
    )
    (net (code "39") (name "/TX-AVR-3.3V") (class "Default")
      (node (ref "IC5") (pin "14") (pinfunction "SCL/IO5_14") (pintype "bidirectional"))
      (node (ref "R5") (pin "2") (pinfunction "2_2") (pintype "passive"))
      (node (ref "T4") (pin "2") (pinfunction "S_2") (pintype "passive"))
    )
    (net (code "40") (name "/TX-AVR-5V") (class "Default")
      (node (ref "IC7") (pin "21") (pinfunction "(TXD1/INT3)PD3_21") (pintype "bidirectional"))
      (node (ref "R6") (pin "2") (pinfunction "2_2") (pintype "passive"))
      (node (ref "T4") (pin "3") (pinfunction "D_3") (pintype "passive"))
    )
    (net (code "41") (name "/TX-ESP-HW") (class "Default")
      (node (ref "IC5") (pin "12") (pinfunction "TXD0/IO1_12") (pintype "bidirectional"))
      (node (ref "R20") (pin "2") (pinfunction "2_2") (pintype "passive"))
    )
    (net (code "42") (name "/UD+") (class "Default")
      (node (ref "IC2") (pin "5") (pinfunction "UD+_5") (pintype "bidirectional"))
      (node (ref "R22") (pin "1") (pinfunction "1_1") (pintype "passive"))
    )
    (net (code "43") (name "/UD-") (class "Default")
      (node (ref "IC2") (pin "6") (pinfunction "UD-_6") (pintype "bidirectional"))
      (node (ref "R23") (pin "1") (pinfunction "1_1") (pintype "passive"))
    )
    (net (code "44") (name "/VBUS") (class "Default")
      (node (ref "AVR") (pin "+5V") (pinfunction "+5V_+5V") (pintype "passive"))
      (node (ref "C24") (pin "2") (pinfunction "2_2") (pintype "passive"))
      (node (ref "IC7") (pin "7") (pinfunction "VBUS_7") (pintype "power_in"))
    )
    (net (code "45") (name "/VIN") (class "Default")
      (node (ref "IN") (pin "1") (pinfunction "1_1") (pintype "passive"))
      (node (ref "R30") (pin "2") (pinfunction "2_2") (pintype "passive"))
      (node (ref "T1") (pin "C") (pinfunction "D_C") (pintype "passive"))
    )
    (net (code "46") (name "/VUSB_ESP") (class "Default")
      (node (ref "C28") (pin "1") (pinfunction "1_1") (pintype "passive"))
      (node (ref "C29") (pin "1") (pinfunction "1_1") (pintype "passive"))
      (node (ref "ESP") (pin "+5V") (pinfunction "+5V_+5V") (pintype "passive"))
      (node (ref "IC2") (pin "16") (pinfunction "VCC_16") (pintype "power_in"))
    )
    (net (code "47") (name "Net-(AVR-PadD+)") (class "Default")
      (node (ref "AVR") (pin "D+") (pinfunction "D+_D+") (pintype "bidirectional"))
      (node (ref "R16") (pin "2") (pinfunction "2_2") (pintype "passive"))
    )
    (net (code "48") (name "Net-(AVR-PadD-)") (class "Default")
      (node (ref "AVR") (pin "D-") (pinfunction "D-_D-") (pintype "bidirectional"))
      (node (ref "R17") (pin "2") (pinfunction "2_2") (pintype "passive"))
    )
    (net (code "49") (name "Net-(AVR-PadSH1)") (class "Default")
      (node (ref "AVR") (pin "SH1") (pinfunction "SH1_SH1") (pintype "passive"))
      (node (ref "AVR") (pin "SH2") (pinfunction "SH2_SH2") (pintype "passive"))
      (node (ref "C25") (pin "1") (pinfunction "1_1") (pintype "passive"))
      (node (ref "R19") (pin "1") (pinfunction "1_1") (pintype "passive"))
    )
    (net (code "50") (name "Net-(BR2-PadAC1)") (class "Default")
      (node (ref "BR2") (pin "AC1") (pinfunction "AC1_AC1") (pintype "passive"))
      (node (ref "F4") (pin "3") (pinfunction "2_3") (pintype "passive"))
      (node (ref "F4") (pin "4") (pinfunction "2_4") (pintype "passive"))
    )
    (net (code "51") (name "Net-(BR2-PadAC2)") (class "Default")
      (node (ref "BR2") (pin "AC2") (pinfunction "AC2_AC2") (pintype "passive"))
      (node (ref "TR1") (pin "4") (pinfunction "4_4") (pintype "passive"))
      (node (ref "TR1") (pin "6") (pinfunction "6_6") (pintype "passive"))
    )
    (net (code "52") (name "Net-(C27-Pad1)") (class "Default")
      (node (ref "C27") (pin "1") (pinfunction "1_1") (pintype "passive"))
      (node (ref "ESP") (pin "SH1") (pinfunction "SH1_SH1") (pintype "passive"))
      (node (ref "ESP") (pin "SH2") (pinfunction "SH2_SH2") (pintype "passive"))
      (node (ref "R24") (pin "1") (pinfunction "1_1") (pintype "passive"))
    )
    (net (code "53") (name "Net-(ESP-PadD+)") (class "Default")
      (node (ref "ESP") (pin "D+") (pinfunction "D+_D+") (pintype "bidirectional"))
      (node (ref "R22") (pin "2") (pinfunction "2_2") (pintype "passive"))
    )
    (net (code "54") (name "Net-(ESP-PadD-)") (class "Default")
      (node (ref "ESP") (pin "D-") (pinfunction "D-_D-") (pintype "bidirectional"))
      (node (ref "R23") (pin "2") (pinfunction "2_2") (pintype "passive"))
    )
    (net (code "55") (name "Net-(F4-1-Pad2)") (class "Default")
      (node (ref "F4") (pin "1") (pinfunction "1_1") (pintype "passive"))
      (node (ref "F4") (pin "2") (pinfunction "1_2") (pintype "passive"))
      (node (ref "TR1") (pin "3") (pinfunction "3_3") (pintype "passive"))
      (node (ref "TR1") (pin "5") (pinfunction "5_5") (pintype "passive"))
    )
    (net (code "56") (name "Net-(FAN-Pad2)") (class "Default")
      (node (ref "FAN") (pin "2") (pinfunction "2_2") (pintype "passive"))
      (node (ref "R13") (pin "1") (pinfunction "1_1") (pintype "passive"))
    )
    (net (code "57") (name "Net-(IC1-SPI2C)") (class "Default")
      (node (ref "C4") (pin "1") (pinfunction "1_1") (pintype "passive"))
      (node (ref "C8") (pin "1") (pinfunction "1_1") (pintype "passive"))
      (node (ref "IC1") (pin "1") (pinfunction "VDD_1") (pintype "power_in"))
      (node (ref "IC1") (pin "5") (pinfunction "SPI2C_5") (pintype "bidirectional"))
      (node (ref "L1") (pin "1") (pinfunction "1_1") (pintype "passive"))
    )
    (net (code "58") (name "Net-(IC1-VREFIO)") (class "Default")
      (node (ref "C5") (pin "1") (pinfunction "1_1") (pintype "passive"))
      (node (ref "IC1") (pin "10") (pinfunction "VREFIO_10") (pintype "bidirectional"))
    )
    (net (code "59") (name "Net-(IC2-DTR)") (class "Default")
      (node (ref "IC2") (pin "13") (pinfunction "DTR_13") (pintype "bidirectional"))
      (node (ref "R25") (pin "2") (pinfunction "2_2") (pintype "passive"))
      (node (ref "T6") (pin "E") (pinfunction "E_E") (pintype "passive"))
    )
    (net (code "60") (name "Net-(IC2-RTS)") (class "Default")
      (node (ref "IC2") (pin "14") (pinfunction "RTS_14") (pintype "bidirectional"))
      (node (ref "R26") (pin "2") (pinfunction "2_2") (pintype "passive"))
      (node (ref "T5") (pin "E") (pinfunction "E_E") (pintype "passive"))
    )
    (net (code "61") (name "Net-(IC2-RXD)") (class "Default")
      (node (ref "IC2") (pin "3") (pinfunction "RXD_3") (pintype "bidirectional"))
      (node (ref "R20") (pin "1") (pinfunction "1_1") (pintype "passive"))
    )
    (net (code "62") (name "Net-(IC2-TXD)") (class "Default")
      (node (ref "IC2") (pin "2") (pinfunction "TXD_2") (pintype "bidirectional"))
      (node (ref "R21") (pin "1") (pinfunction "1_1") (pintype "passive"))
    )
    (net (code "63") (name "Net-(IC2-V3)") (class "Default")
      (node (ref "C26") (pin "1") (pinfunction "1_1") (pintype "passive"))
      (node (ref "IC2") (pin "4") (pinfunction "V3_4") (pintype "bidirectional"))
    )
    (net (code "64") (name "Net-(IC3A--IN)") (class "Default")
      (node (ref "C18") (pin "2") (pinfunction "2_2") (pintype "passive"))
      (node (ref "IC3") (pin "2") (pinfunction "-IN_2") (pintype "input"))
      (node (ref "R1") (pin "2") (pinfunction "2_2") (pintype "passive"))
    )
    (net (code "65") (name "Net-(IC3A-OUT)") (class "Default")
      (node (ref "C18") (pin "1") (pinfunction "1_1") (pintype "passive"))
      (node (ref "IC3") (pin "1") (pinfunction "OUT_1") (pintype "output"))
      (node (ref "R11") (pin "1") (pinfunction "1_1") (pintype "passive"))
    )
    (net (code "66") (name "Net-(IC3B-+IN)") (class "Default")
      (node (ref "IC3") (pin "5") (pinfunction "+IN_5") (pintype "input"))
      (node (ref "R1") (pin "1") (pinfunction "1_1") (pintype "passive"))
      (node (ref "R4") (pin "1") (pinfunction "1_1") (pintype "passive"))
      (node (ref "T1") (pin "E") (pinfunction "S_E") (pintype "passive"))
    )
    (net (code "67") (name "Net-(IC3B--IN)") (class "Default")
      (node (ref "IC3") (pin "6") (pinfunction "-IN_6") (pintype "input"))
      (node (ref "R40") (pin "1") (pinfunction "1_1") (pintype "passive"))
      (node (ref "R41") (pin "1") (pinfunction "1_1") (pintype "passive"))
      (node (ref "T11") (pin "E") (pinfunction "E_E") (pintype "passive"))
    )
    (net (code "68") (name "Net-(IC3B-OUT)") (class "Default")
      (node (ref "IC3") (pin "7") (pinfunction "OUT_7") (pintype "output"))
      (node (ref "T11") (pin "B") (pinfunction "B_B") (pintype "passive"))
    )
    (net (code "69") (name "Net-(IC3C--IN)") (class "Default")
      (node (ref "IC3") (pin "9") (pinfunction "-IN_9") (pintype "input"))
      (node (ref "R35") (pin "1") (pinfunction "1_1") (pintype "passive"))
      (node (ref "R37") (pin "1") (pinfunction "1_1") (pintype "passive"))
      (node (ref "T2") (pin "E") (pinfunction "E_E") (pintype "passive"))
    )
    (net (code "70") (name "Net-(IC3C-OUT)") (class "Default")
      (node (ref "IC3") (pin "8") (pinfunction "OUT_8") (pintype "output"))
      (node (ref "T2") (pin "B") (pinfunction "B_B") (pintype "passive"))
    )
    (net (code "71") (name "Net-(IC3D--IN)") (class "Default")
      (node (ref "IC3") (pin "13") (pinfunction "-IN_13") (pintype "input"))
      (node (ref "IC3") (pin "14") (pinfunction "OUT_14") (pintype "output"))
    )
    (net (code "72") (name "Net-(IC7-(~{HWB})PE2)") (class "Default")
      (node (ref "IC7") (pin "33") (pinfunction "(~{HWB})PE2_33") (pintype "bidirectional"))
      (node (ref "R18") (pin "1") (pinfunction "1_1") (pintype "passive"))
    )
    (net (code "73") (name "Net-(IC7-AREF)") (class "Default")
      (node (ref "C17") (pin "1") (pinfunction "1_1") (pintype "passive"))
      (node (ref "IC7") (pin "42") (pinfunction "AREF_42") (pintype "passive"))
    )
    (net (code "74") (name "Net-(IC7-UCAP)") (class "Default")
      (node (ref "C32") (pin "2") (pinfunction "2_2") (pintype "passive"))
      (node (ref "IC7") (pin "6") (pinfunction "UCAP_6") (pintype "power_in"))
    )
    (net (code "75") (name "Net-(IC7-XTAL1)") (class "Default")
      (node (ref "C14") (pin "2") (pinfunction "2_2") (pintype "passive"))
      (node (ref "IC7") (pin "17") (pinfunction "XTAL1_17") (pintype "bidirectional"))
      (node (ref "Q1") (pin "2") (pinfunction "2_2") (pintype "passive"))
    )
    (net (code "76") (name "Net-(IC7-XTAL2)") (class "Default")
      (node (ref "C15") (pin "2") (pinfunction "2_2") (pintype "passive"))
      (node (ref "IC7") (pin "16") (pinfunction "XTAL2_16") (pintype "bidirectional"))
      (node (ref "Q1") (pin "1") (pinfunction "1_1") (pintype "passive"))
    )
    (net (code "77") (name "Net-(IC18-VDD)") (class "Default")
      (node (ref "C21") (pin "1") (pinfunction "1_1") (pintype "passive"))
      (node (ref "C9") (pin "1") (pinfunction "1_1") (pintype "passive"))
      (node (ref "IC18") (pin "8") (pinfunction "VDD_8") (pintype "bidirectional"))
      (node (ref "L5") (pin "1") (pinfunction "1_1") (pintype "passive"))
    )
    (net (code "78") (name "Net-(R25-Pad1)") (class "Default")
      (node (ref "R25") (pin "1") (pinfunction "1_1") (pintype "passive"))
      (node (ref "T5") (pin "B") (pinfunction "B_B") (pintype "passive"))
    )
    (net (code "79") (name "Net-(R26-Pad1)") (class "Default")
      (node (ref "R26") (pin "1") (pinfunction "1_1") (pintype "passive"))
      (node (ref "T6") (pin "B") (pinfunction "B_B") (pintype "passive"))
    )
    (net (code "80") (name "Net-(T1-G)") (class "Default")
      (node (ref "R11") (pin "2") (pinfunction "2_2") (pintype "passive"))
      (node (ref "T1") (pin "B") (pinfunction "G_B") (pintype "passive"))
    )
    (net (code "81") (name "UGND") (class "Default")
      (node (ref "AVR") (pin "GND") (pinfunction "GND_GND") (pintype "passive"))
      (node (ref "C1") (pin "1") (pinfunction "1_1") (pintype "passive"))
      (node (ref "C24") (pin "1") (pinfunction "1_1") (pintype "passive"))
      (node (ref "C25") (pin "2") (pinfunction "2_2") (pintype "passive"))
      (node (ref "C27") (pin "2") (pinfunction "2_2") (pintype "passive"))
      (node (ref "C32") (pin "1") (pinfunction "1_1") (pintype "passive"))
      (node (ref "ESP") (pin "GND") (pinfunction "GND_GND") (pintype "passive"))
      (node (ref "IC7") (pin "5") (pinfunction "UGND_5") (pintype "power_in"))
      (node (ref "R19") (pin "2") (pinfunction "2_2") (pintype "passive"))
      (node (ref "R24") (pin "2") (pinfunction "2_2") (pintype "passive"))
    )
    (net (code "82") (name "VSS") (class "Default")
      (node (ref "BR2") (pin "DC-") (pinfunction "DC-_DC-") (pintype "passive"))
      (node (ref "C10") (pin "1") (pinfunction "1_1") (pintype "passive"))
      (node (ref "C11") (pin "1") (pinfunction "1_1") (pintype "passive"))
      (node (ref "C12") (pin "2") (pinfunction "2_2") (pintype "passive"))
      (node (ref "C13") (pin "2") (pinfunction "2_2") (pintype "passive"))
      (node (ref "C14") (pin "1") (pinfunction "1_1") (pintype "passive"))
      (node (ref "C15") (pin "1") (pinfunction "1_1") (pintype "passive"))
      (node (ref "C16") (pin "2") (pinfunction "2_2") (pintype "passive"))
      (node (ref "C17") (pin "2") (pinfunction "2_2") (pintype "passive"))
      (node (ref "C19") (pin "2") (pinfunction "2_2") (pintype "passive"))
      (node (ref "C2") (pin "2") (pinfunction "2_2") (pintype "passive"))
      (node (ref "C20") (pin "2") (pinfunction "2_2") (pintype "passive"))
      (node (ref "C21") (pin "2") (pinfunction "2_2") (pintype "passive"))
      (node (ref "C22") (pin "2") (pinfunction "2_2") (pintype "passive"))
      (node (ref "C23") (pin "2") (pinfunction "2_2") (pintype "passive"))
      (node (ref "C26") (pin "2") (pinfunction "2_2") (pintype "passive"))
      (node (ref "C28") (pin "2") (pinfunction "2_2") (pintype "passive"))
      (node (ref "C29") (pin "2") (pinfunction "2_2") (pintype "passive"))
      (node (ref "C3") (pin "-") (pinfunction "-_-") (pintype "passive"))
      (node (ref "C30") (pin "2") (pinfunction "2_2") (pintype "passive"))
      (node (ref "C31") (pin "2") (pinfunction "2_2") (pintype "passive"))
      (node (ref "C4") (pin "2") (pinfunction "2_2") (pintype "passive"))
      (node (ref "C47") (pin "2") (pinfunction "2_2") (pintype "passive"))
      (node (ref "C48") (pin "1") (pinfunction "1_1") (pintype "passive"))
      (node (ref "C5") (pin "2") (pinfunction "2_2") (pintype "passive"))
      (node (ref "C51") (pin "2") (pinfunction "2_2") (pintype "passive"))
      (node (ref "C6") (pin "2") (pinfunction "2_2") (pintype "passive"))
      (node (ref "C7") (pin "2") (pinfunction "2_2") (pintype "passive"))
      (node (ref "C8") (pin "2") (pinfunction "2_2") (pintype "passive"))
      (node (ref "C9") (pin "2") (pinfunction "2_2") (pintype "passive"))
      (node (ref "FAN") (pin "1") (pinfunction "1_1") (pintype "passive"))
      (node (ref "IC1") (pin "4") (pinfunction "AGND_4") (pintype "power_in"))
      (node (ref "IC18") (pin "1") (pinfunction "ADDR_1") (pintype "bidirectional"))
      (node (ref "IC18") (pin "3") (pinfunction "VSS_3") (pintype "bidirectional"))
      (node (ref "IC18") (pin "5") (pinfunction "AIN1_5") (pintype "bidirectional"))
      (node (ref "IC18") (pin "7") (pinfunction "AIN3_7") (pintype "bidirectional"))
      (node (ref "IC2") (pin "1") (pinfunction "GND_1") (pintype "power_in"))
      (node (ref "IC3") (pin "11") (pinfunction "V-_11") (pintype "power_in"))
      (node (ref "IC4") (pin "2") (pinfunction "GND_2") (pintype "passive"))
      (node (ref "IC5") (pin "13") (pinfunction "GND_13") (pintype "power_in"))
      (node (ref "IC5") (pin "18") (pinfunction "GND_18") (pintype "power_in"))
      (node (ref "IC5") (pin "9") (pinfunction "GND_9") (pintype "power_in"))
      (node (ref "IC5") (pin "TP") (pinfunction "GND_TP") (pintype "power_in"))
      (node (ref "IC6") (pin "1") (pinfunction "VSS_1") (pintype "input"))
      (node (ref "IC7") (pin "15") (pinfunction "GND_15") (pintype "power_in"))
      (node (ref "IC7") (pin "23") (pinfunction "GND_23") (pintype "power_in"))
      (node (ref "IC7") (pin "35") (pinfunction "GND_35") (pintype "power_in"))
      (node (ref "IC7") (pin "43") (pinfunction "GND_43") (pintype "power_in"))
      (node (ref "IC8") (pin "1") (pinfunction "A0_1") (pintype "input"))
      (node (ref "IC8") (pin "2") (pinfunction "A1_2") (pintype "input"))
      (node (ref "IC8") (pin "3") (pinfunction "A2_3") (pintype "input"))
      (node (ref "IC8") (pin "4") (pinfunction "GND_4") (pintype "power_in"))
      (node (ref "IC8") (pin "7") (pinfunction "WP_7") (pintype "input"))
      (node (ref "IC9") (pin "2") (pinfunction "A1_2") (pintype "input"))
      (node (ref "IC9") (pin "3") (pinfunction "A2_3") (pintype "input"))
      (node (ref "IC9") (pin "4") (pinfunction "GND_4") (pintype "power_in"))
      (node (ref "IC9") (pin "7") (pinfunction "WP_7") (pintype "input"))
      (node (ref "IN") (pin "2") (pinfunction "2_2") (pintype "passive"))
      (node (ref "ISP") (pin "6") (pinfunction "6_6") (pintype "passive"))
      (node (ref "PANEL") (pin "16") (pinfunction "16_16") (pintype "passive"))
      (node (ref "PANEL") (pin "17") (pinfunction "17_17") (pintype "passive"))
      (node (ref "PANEL") (pin "18") (pinfunction "18_18") (pintype "passive"))
      (node (ref "PANEL") (pin "19") (pinfunction "19_19") (pintype "passive"))
      (node (ref "PANEL") (pin "2") (pinfunction "2_2") (pintype "passive"))
      (node (ref "PANEL") (pin "20") (pinfunction "20_20") (pintype "passive"))
      (node (ref "PRG-ESP") (pin "1") (pinfunction "1_1") (pintype "passive"))
      (node (ref "R10") (pin "1") (pinfunction "1_1") (pintype "passive"))
      (node (ref "R18") (pin "2") (pinfunction "2_2") (pintype "passive"))
      (node (ref "R32") (pin "1") (pinfunction "1_1") (pintype "passive"))
      (node (ref "R35") (pin "2") (pinfunction "2_2") (pintype "passive"))
      (node (ref "R4") (pin "2") (pinfunction "2_2") (pintype "passive"))
      (node (ref "R40") (pin "2") (pinfunction "2_2") (pintype "passive"))
      (node (ref "RST-AVR") (pin "1") (pinfunction "1_1") (pintype "passive"))
      (node (ref "RST-ESP") (pin "1") (pinfunction "1_1") (pintype "passive"))
    )
    (net (code "83") (name "unconnected-(HS1-Pad1)") (class "Default")
      (node (ref "HS1") (pin "1") (pinfunction "1_1") (pintype "passive"))
    )
    (net (code "84") (name "unconnected-(HS1-Pad2)") (class "Default")
      (node (ref "HS1") (pin "2") (pinfunction "2_2") (pintype "passive"))
    )
    (net (code "85") (name "unconnected-(IC2-CTS-Pad9)") (class "Default")
      (node (ref "IC2") (pin "9") (pinfunction "CTS_9") (pintype "bidirectional"))
    )
    (net (code "86") (name "unconnected-(IC2-DCD-Pad12)") (class "Default")
      (node (ref "IC2") (pin "12") (pinfunction "DCD_12") (pintype "bidirectional"))
    )
    (net (code "87") (name "unconnected-(IC2-DSR-Pad10)") (class "Default")
      (node (ref "IC2") (pin "10") (pinfunction "DSR_10") (pintype "bidirectional"))
    )
    (net (code "88") (name "unconnected-(IC2-NC1-Pad8)") (class "Default")
      (node (ref "IC2") (pin "8") (pinfunction "NC1_8") (pintype "no_connect"))
    )
    (net (code "89") (name "unconnected-(IC2-NC2-Pad7)") (class "Default")
      (node (ref "IC2") (pin "7") (pinfunction "NC2_7") (pintype "no_connect"))
    )
    (net (code "90") (name "unconnected-(IC2-R232-Pad15)") (class "Default")
      (node (ref "IC2") (pin "15") (pinfunction "R232_15") (pintype "bidirectional"))
    )
    (net (code "91") (name "unconnected-(IC2-RI-Pad11)") (class "Default")
      (node (ref "IC2") (pin "11") (pinfunction "RI_11") (pintype "bidirectional"))
    )
    (net (code "92") (name "unconnected-(IC5-ADC{slash}TOUT-Pad16)") (class "Default")
      (node (ref "IC5") (pin "16") (pinfunction "ADC/TOUT_16") (pintype "bidirectional"))
    )
    (net (code "93") (name "unconnected-(IC5-MISO{slash}IO12-Pad4)") (class "Default")
      (node (ref "IC5") (pin "4") (pinfunction "MISO/IO12_4") (pintype "bidirectional"))
    )
    (net (code "94") (name "unconnected-(IC5-MOSI{slash}IO13-Pad5)") (class "Default")
      (node (ref "IC5") (pin "5") (pinfunction "MOSI/IO13_5") (pintype "bidirectional"))
    )
    (net (code "95") (name "unconnected-(IC5-SCK{slash}IO14-Pad3)") (class "Default")
      (node (ref "IC5") (pin "3") (pinfunction "SCK/IO14_3") (pintype "bidirectional"))
    )
    (net (code "96") (name "unconnected-(IC5-WAKE{slash}IO16-Pad17)") (class "Default")
      (node (ref "IC5") (pin "17") (pinfunction "WAKE/IO16_17") (pintype "bidirectional"))
    )
    (net (code "97") (name "unconnected-(IC7-(ADC5{slash}TMS)PF5-Pad38)") (class "Default")
      (node (ref "IC7") (pin "38") (pinfunction "(ADC5/TMS)PF5_38") (pintype "bidirectional"))
    )
    (net (code "98") (name "unconnected-(IC7-(ADC6{slash}TDO)PF6-Pad37)") (class "Default")
      (node (ref "IC7") (pin "37") (pinfunction "(ADC6/TDO)PF6_37") (pintype "bidirectional"))
    )
    (net (code "99") (name "unconnected-(IC7-(ADC7(TDI)PF7-Pad36)") (class "Default")
      (node (ref "IC7") (pin "36") (pinfunction "(ADC7(TDI)PF7_36") (pintype "bidirectional"))
    )
    (net (code "100") (name "unconnected-(IC7-(RTS{slash}OC0A{slash}OC1C)PB7-Pad12)") (class "Default")
      (node (ref "IC7") (pin "12") (pinfunction "(RTS/OC0A/OC1C)PB7_12") (pintype "bidirectional"))
    )
    (net (code "101") (name "unconnected-(IC7-(SS)PB0-Pad8)") (class "Default")
      (node (ref "IC7") (pin "8") (pinfunction "(SS)PB0_8") (pintype "bidirectional"))
    )
    (net (code "102") (name "unconnected-(IC18-ALERT{slash}RDY-Pad2)") (class "Default")
      (node (ref "IC18") (pin "2") (pinfunction "ALERT/RDY_2") (pintype "bidirectional"))
    )
  )
)
